# RTU_LMG_Microcontroller.net
KiCad netlist of a schematic drawn in Altium Designer
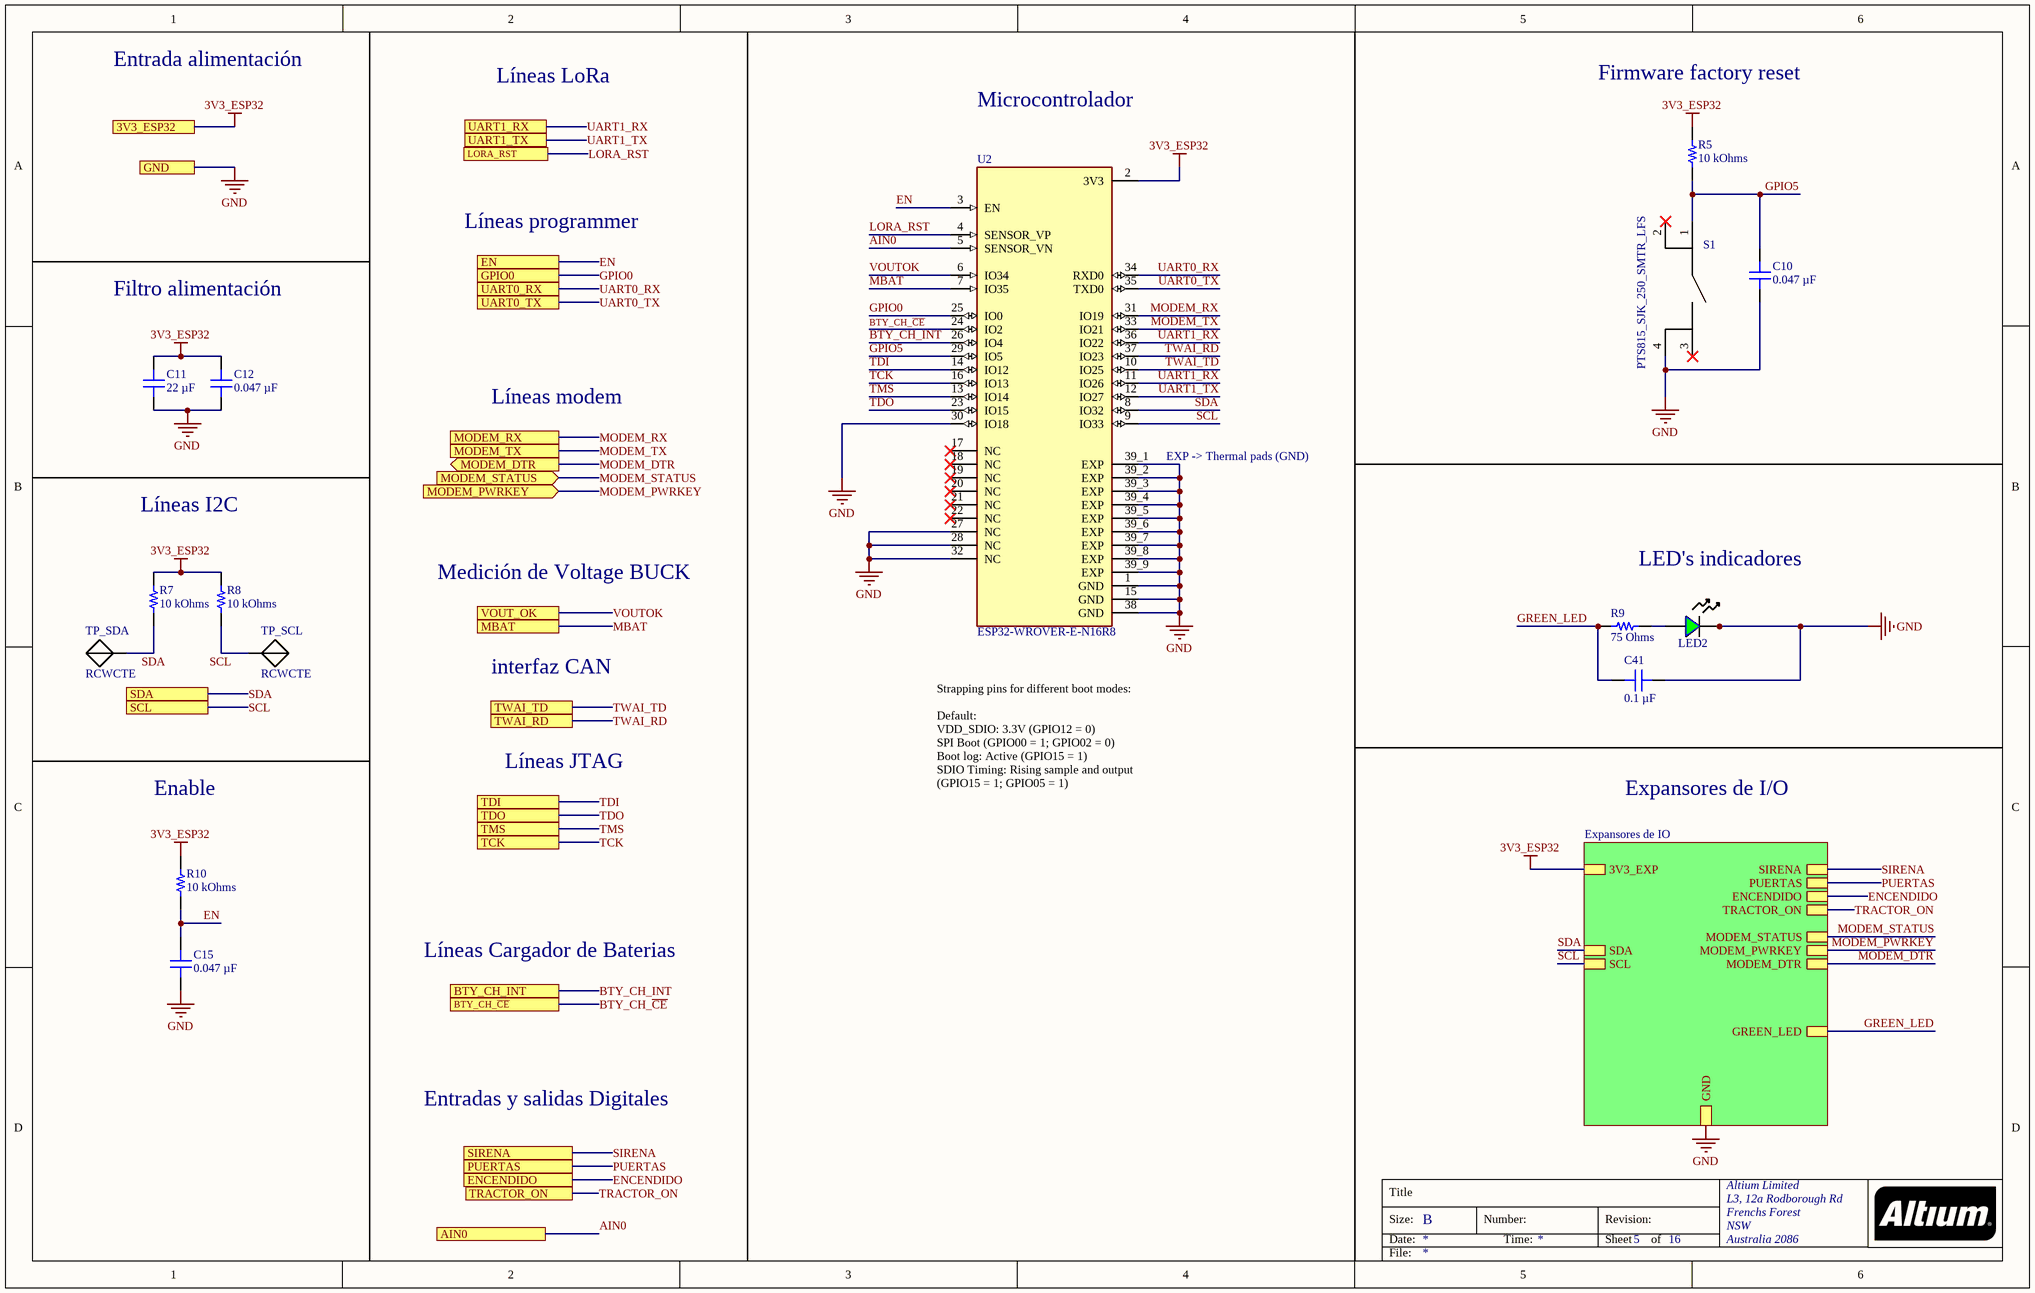
[diagram p0: RTU_LMG_Microcontroller.SchDoc]

(export (version "E")
  (design (tool "Eeschema 10.0.6"))
  (components
    (comp (ref "C10")
      (value "0.047 µF")
      (footprint "CAP 0603_1608")
      (description "CAP CER 0.047UF 100V X7R 0603")
      (fields (field (name "PART NUMBER") "885012206118") (field (name "MANUFACTURER") "Würth Elektronik"))
      (libsource (lib "Celestial Altium Library - altium_library") (part "Capacitor"))
    )
    (comp (ref "C11")
      (value "22 µF")
      (footprint "CAP 0805_2012")
      (description "CAP CER 22UF 16V X5R 0805")
      (fields
        (field (name "PART NUMBER") "CL21A226MOCLRNC")
        (field (name "MANUFACTURER") "Samsung Electro-Mechanics")
      )
      (libsource (lib "Celestial Altium Library - altium_library") (part "Capacitor"))
    )
    (comp (ref "C12")
      (value "0.047 µF")
      (footprint "CAP 0603_1608")
      (description "CAP CER 0.047UF 100V X7R 0603")
      (fields (field (name "PART NUMBER") "885012206118") (field (name "MANUFACTURER") "Würth Elektronik"))
      (libsource (lib "Celestial Altium Library - altium_library") (part "Capacitor"))
    )
    (comp (ref "C15")
      (value "0.047 µF")
      (footprint "CAP 0603_1608")
      (description "CAP CER 0.047UF 100V X7R 0603")
      (fields (field (name "PART NUMBER") "885012206118") (field (name "MANUFACTURER") "Würth Elektronik"))
      (libsource (lib "Celestial Altium Library - altium_library") (part "Capacitor"))
    )
    (comp (ref "C41")
      (value "0.1 µF")
      (footprint "CAP 0402_1005")
      (description "CAP CER 0.1UF 50V X5R 0402")
      (fields
        (field (name "PART NUMBER") "CGA2B3X5R1H104M050BB")
        (field (name "CAPACITANCE") "0.1 µF")
        (field (name "MANUFACTURER") "TDK Corporation")
      )
      (libsource (lib "Celestial Altium Library - altium_library") (part "Capacitor"))
    )
    (comp (ref "LED2")
      (value "LTST-C170GKT")
      (footprint "0805 SMD - LED")
      (description "LED verde SMD (0805)")
      (fields (field (name "COPYRIGHT") "Copyright (C) 2023 Ultra Librarian. All rights reserved."))
      (libsource (lib "DIN_DC_Base_Board_components_SCH_footprints") (part "LTST-C170GKT"))
    )
    (comp (ref "R5")
      (value "10 kOhms")
      (footprint "RES 0603_1608")
      (description "RES 10K OHM 1% 1/10W 0603")
      (fields (field (name "PART NUMBER") "RC0603FR-0710KL") (field (name "MANUFACTURER") "Yageo"))
      (libsource (lib "Celestial Altium Library - altium_library") (part "Resistor"))
    )
    (comp (ref "R7")
      (value "10 kOhms")
      (footprint "RES 0603_1608")
      (description "RES 10K OHM 1% 1/10W 0603")
      (fields (field (name "PART NUMBER") "RC0603FR-0710KL") (field (name "MANUFACTURER") "Yageo"))
      (libsource (lib "Celestial Altium Library - altium_library") (part "Resistor"))
    )
    (comp (ref "R8")
      (value "10 kOhms")
      (footprint "RES 0603_1608")
      (description "RES 10K OHM 1% 1/10W 0603")
      (fields (field (name "PART NUMBER") "RC0603FR-0710KL") (field (name "MANUFACTURER") "Yageo"))
      (libsource (lib "Celestial Altium Library - altium_library") (part "Resistor"))
    )
    (comp (ref "R9")
      (value "75 Ohms")
      (footprint "RES 0402_1005")
      (description "RES 75 OHM 1% 1/16W 0402")
      (fields (field (name "PART NUMBER") "CRCW040275R0FKEDC") (field (name "MANUFACTURER") "Vishay Dale"))
      (libsource (lib "Celestial Altium Library - altium_library") (part "Resistor"))
    )
    (comp (ref "R10")
      (value "10 kOhms")
      (footprint "RES 0603_1608")
      (description "RES 10K OHM 1% 1/10W 0603")
      (fields (field (name "PART NUMBER") "RC0603FR-0710KL") (field (name "MANUFACTURER") "Yageo"))
      (libsource (lib "Celestial Altium Library - altium_library") (part "Resistor"))
    )
    (comp (ref "S1")
      (value "PTS815_SJK_250_SMTR_LFS")
      (footprint "PTS815SJK250SMTRLFS")
      (description "Switch")
      (fields
        (field (name "MANUFACTURER_PART_NUMBER") "PTS815 SJK 250 SMTR LFS")
        (field (name "MOUSER PART NUMBER") "611-PTS815SJK250SMTR")
      )
      (libsource (lib "DIN_DC_Base_Board_components") (part "PTS815_SJK_250_SMTR_LFS"))
    )
    (comp (ref "TP_SCL")
      (value "RCWCTE")
      (footprint "RCWCTE")
      (description "- PC Test Point - - Plating Surface Mount Mounting Type")
      (fields (field (name "MF") "KOA Speer") (field (name "DIGI-KEY_PART_NUMBER") "2019-RCWCTETR-ND"))
      (libsource (lib "DIN_DC_Base_Board_components") (part "RCWCTE"))
    )
    (comp (ref "TP_SDA")
      (value "RCWCTE")
      (footprint "RCWCTE")
      (description "- PC Test Point - - Plating Surface Mount Mounting Type")
      (fields (field (name "MF") "KOA Speer") (field (name "DIGI-KEY_PART_NUMBER") "2019-RCWCTETR-ND"))
      (libsource (lib "DIN_DC_Base_Board_components") (part "RCWCTE"))
    )
    (comp (ref "U2")
      (value "ESP32-WROVER-E-N16R8")
      (footprint "ESP32-WROVER-E-N16R8")
      (libsource (lib "DIN_DC_Base_Board_components_SCH_footprints") (part "ESP32-WROVER-E-N16R8"))
    )
  )
  (nets
    (net (code "1") (name "/AIN0") (class "Default")
      (node (ref "U2") (pin "5") (pinfunction "SENSOR_VN_5") (pintype "input"))
    )
    (net (code "2") (name "/BTY_CH_INT") (class "Default")
      (node (ref "U2") (pin "26") (pinfunction "IO4_26") (pintype "bidirectional"))
    )
    (net (code "3") (name "/BTY_CH_~{CE}") (class "Default")
      (node (ref "U2") (pin "24") (pinfunction "IO2_24") (pintype "bidirectional"))
    )
    (net (code "4") (name "/EN") (class "Default")
      (node (ref "C15") (pin "2") (pinfunction "2_2") (pintype "passive"))
      (node (ref "R10") (pin "1") (pinfunction "1_1") (pintype "passive"))
      (node (ref "U2") (pin "3") (pinfunction "EN_3") (pintype "input"))
    )
    (net (code "6") (name "/GPIO0") (class "Default")
      (node (ref "U2") (pin "25") (pinfunction "IO0_25") (pintype "bidirectional"))
    )
    (net (code "7") (name "/GPIO5") (class "Default")
      (node (ref "C10") (pin "2") (pinfunction "2_2") (pintype "passive"))
      (node (ref "R5") (pin "1") (pinfunction "1_1") (pintype "passive"))
      (node (ref "S1") (pin "1") (pinfunction "COM_1_1") (pintype "passive"))
      (node (ref "U2") (pin "29") (pinfunction "IO5_29") (pintype "bidirectional"))
    )
    (net (code "8") (name "/GREEN_LED") (class "Default")
      (node (ref "C41") (pin "2") (pinfunction "2_2") (pintype "passive"))
      (node (ref "R9") (pin "1") (pinfunction "1_1") (pintype "passive"))
    )
    (net (code "9") (name "/LORA_RST") (class "Default")
      (node (ref "U2") (pin "4") (pinfunction "SENSOR_VP_4") (pintype "input"))
    )
    (net (code "10") (name "/MBAT") (class "Default")
      (node (ref "U2") (pin "7") (pinfunction "IO35_7") (pintype "input"))
    )
    (net (code "13") (name "/MODEM_RX") (class "Default")
      (node (ref "U2") (pin "31") (pinfunction "IO19_31") (pintype "bidirectional"))
    )
    (net (code "15") (name "/MODEM_TX") (class "Default")
      (node (ref "U2") (pin "33") (pinfunction "IO21_33") (pintype "bidirectional"))
    )
    (net (code "17") (name "/SCL") (class "Default")
      (node (ref "R8") (pin "1") (pinfunction "1_1") (pintype "passive"))
      (node (ref "TP_SCL") (pin "1") (pinfunction "TP_1") (pintype "passive"))
      (node (ref "U2") (pin "9") (pinfunction "IO33_9") (pintype "bidirectional"))
    )
    (net (code "18") (name "/SDA") (class "Default")
      (node (ref "R7") (pin "1") (pinfunction "1_1") (pintype "passive"))
      (node (ref "TP_SDA") (pin "1") (pinfunction "TP_1") (pintype "passive"))
      (node (ref "U2") (pin "8") (pinfunction "IO32_8") (pintype "bidirectional"))
    )
    (net (code "20") (name "/TCK") (class "Default")
      (node (ref "U2") (pin "16") (pinfunction "IO13_16") (pintype "bidirectional"))
    )
    (net (code "21") (name "/TDI") (class "Default")
      (node (ref "U2") (pin "14") (pinfunction "IO12_14") (pintype "bidirectional"))
    )
    (net (code "22") (name "/TDO") (class "Default")
      (node (ref "U2") (pin "23") (pinfunction "IO15_23") (pintype "bidirectional"))
    )
    (net (code "23") (name "/TMS") (class "Default")
      (node (ref "U2") (pin "13") (pinfunction "IO14_13") (pintype "bidirectional"))
    )
    (net (code "25") (name "/TWAI_RD") (class "Default")
      (node (ref "U2") (pin "37") (pinfunction "IO23_37") (pintype "bidirectional"))
    )
    (net (code "26") (name "/TWAI_TD") (class "Default")
      (node (ref "U2") (pin "10") (pinfunction "IO25_10") (pintype "bidirectional"))
    )
    (net (code "27") (name "/UART0_RX") (class "Default")
      (node (ref "U2") (pin "34") (pinfunction "RXD0_34") (pintype "bidirectional"))
    )
    (net (code "28") (name "/UART0_TX") (class "Default")
      (node (ref "U2") (pin "35") (pinfunction "TXD0_35") (pintype "bidirectional"))
    )
    (net (code "29") (name "/UART1_RX") (class "Default")
      (node (ref "U2") (pin "11") (pinfunction "IO26_11") (pintype "bidirectional"))
      (node (ref "U2") (pin "36") (pinfunction "IO22_36") (pintype "bidirectional"))
    )
    (net (code "30") (name "/UART1_TX") (class "Default")
      (node (ref "U2") (pin "12") (pinfunction "IO27_12") (pintype "bidirectional"))
    )
    (net (code "31") (name "/VOUTOK") (class "Default")
      (node (ref "U2") (pin "6") (pinfunction "IO34_6") (pintype "input"))
    )
    (net (code "32") (name "3V3_ESP32") (class "Default")
      (node (ref "C11") (pin "2") (pinfunction "2_2") (pintype "passive"))
      (node (ref "C12") (pin "2") (pinfunction "2_2") (pintype "passive"))
      (node (ref "R10") (pin "2") (pinfunction "2_2") (pintype "passive"))
      (node (ref "R5") (pin "2") (pinfunction "2_2") (pintype "passive"))
      (node (ref "R7") (pin "2") (pinfunction "2_2") (pintype "passive"))
      (node (ref "R8") (pin "2") (pinfunction "2_2") (pintype "passive"))
      (node (ref "U2") (pin "2") (pinfunction "3V3_2") (pintype "power_in"))
    )
    (net (code "33") (name "GND") (class "Default")
      (node (ref "C10") (pin "1") (pinfunction "1_1") (pintype "passive"))
      (node (ref "C11") (pin "1") (pinfunction "1_1") (pintype "passive"))
      (node (ref "C12") (pin "1") (pinfunction "1_1") (pintype "passive"))
      (node (ref "C15") (pin "1") (pinfunction "1_1") (pintype "passive"))
      (node (ref "C41") (pin "1") (pinfunction "1_1") (pintype "passive"))
      (node (ref "LED2") (pin "K") (pinfunction "CATHODE_K") (pintype "passive"))
      (node (ref "S1") (pin "4") (pinfunction "N.O._2_4") (pintype "passive"))
      (node (ref "U2") (pin "1") (pinfunction "GND_1") (pintype "power_in"))
      (node (ref "U2") (pin "15") (pinfunction "GND_15") (pintype "power_in"))
      (node (ref "U2") (pin "27") (pinfunction "NC_27") (pintype "passive"))
      (node (ref "U2") (pin "28") (pinfunction "NC_28") (pintype "passive"))
      (node (ref "U2") (pin "30") (pinfunction "IO18_30") (pintype "bidirectional"))
      (node (ref "U2") (pin "32") (pinfunction "NC_32") (pintype "passive"))
      (node (ref "U2") (pin "38") (pinfunction "GND_38") (pintype "power_in"))
      (node (ref "U2") (pin "39_1") (pinfunction "EXP_39_1") (pintype "power_in"))
      (node (ref "U2") (pin "39_2") (pinfunction "EXP_39_2") (pintype "power_in"))
      (node (ref "U2") (pin "39_3") (pinfunction "EXP_39_3") (pintype "power_in"))
      (node (ref "U2") (pin "39_4") (pinfunction "EXP_39_4") (pintype "power_in"))
      (node (ref "U2") (pin "39_5") (pinfunction "EXP_39_5") (pintype "power_in"))
      (node (ref "U2") (pin "39_6") (pinfunction "EXP_39_6") (pintype "power_in"))
      (node (ref "U2") (pin "39_7") (pinfunction "EXP_39_7") (pintype "power_in"))
      (node (ref "U2") (pin "39_8") (pinfunction "EXP_39_8") (pintype "power_in"))
      (node (ref "U2") (pin "39_9") (pinfunction "EXP_39_9") (pintype "power_in"))
    )
    (net (code "34") (name "Net-(LED2-ANODE)") (class "Default")
      (node (ref "LED2") (pin "A") (pinfunction "ANODE_A") (pintype "passive"))
      (node (ref "R9") (pin "2") (pinfunction "2_2") (pintype "passive"))
    )
    (net (code "35") (name "unconnected-(S1-COM_2-Pad2)") (class "Default")
      (node (ref "S1") (pin "2") (pinfunction "COM_2_2") (pintype "passive+no_connect"))
    )
    (net (code "36") (name "unconnected-(S1-N.O._1-Pad3)") (class "Default")
      (node (ref "S1") (pin "3") (pinfunction "N.O._1_3") (pintype "passive+no_connect"))
    )
    (net (code "37") (name "unconnected-(U2-NC-Pad17)") (class "Default")
      (node (ref "U2") (pin "17") (pinfunction "NC_17") (pintype "passive+no_connect"))
    )
    (net (code "38") (name "unconnected-(U2-NC-Pad18)") (class "Default")
      (node (ref "U2") (pin "18") (pinfunction "NC_18") (pintype "passive+no_connect"))
    )
    (net (code "39") (name "unconnected-(U2-NC-Pad19)") (class "Default")
      (node (ref "U2") (pin "19") (pinfunction "NC_19") (pintype "passive+no_connect"))
    )
    (net (code "40") (name "unconnected-(U2-NC-Pad20)") (class "Default")
      (node (ref "U2") (pin "20") (pinfunction "NC_20") (pintype "passive+no_connect"))
    )
    (net (code "41") (name "unconnected-(U2-NC-Pad21)") (class "Default")
      (node (ref "U2") (pin "21") (pinfunction "NC_21") (pintype "passive+no_connect"))
    )
    (net (code "42") (name "unconnected-(U2-NC-Pad22)") (class "Default")
      (node (ref "U2") (pin "22") (pinfunction "NC_22") (pintype "passive+no_connect"))
    )
  )
)
